# JL7018F8.net
KiCad netlist of a schematic drawn in Altium Designer
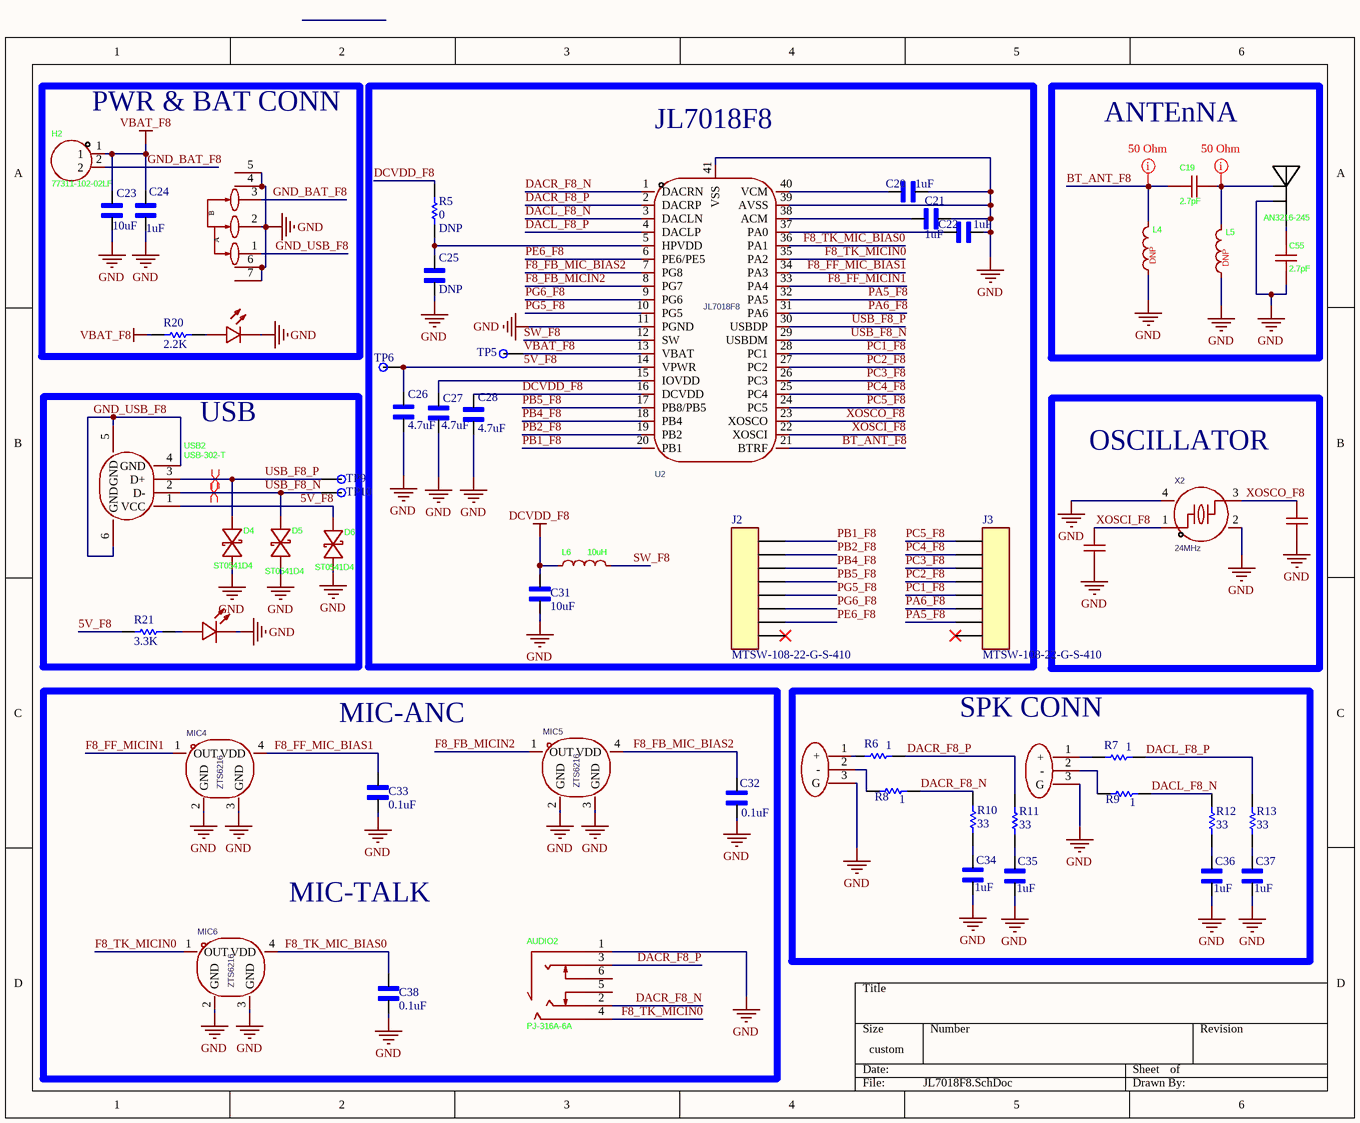
[diagram p0: JL7018F8.SchDoc]

(export (version "E")
  (design (tool "Eeschema 10.0.6"))
  (components
    (comp (ref "ANT2")
      (value "AN3216-245")
      (footprint "CUSTOME ANTEENA")
      (fields (field (name "MANUFACTURER") "Rainsun(霖昱微)") (field (name "POWER") "1W"))
      (libsource (lib "JEILI_DEV_BOARD") (part "AN3216-245"))
    )
    (comp (ref "AUDIO2")
      (value "PJ-316A-6A")
      (footprint "AUDIO-SMD_PJ-316A-6A")
      (fields (field (name "MANUFACTURER") "韩国韩荣"))
      (libsource (lib "JEILI_DEV_BOARD") (part "PJ-316A-6A"))
    )
    (comp (ref "C19")
      (value "2.7pF")
      (footprint "C0603")
      (fields (field (name "MANUFACTURER") "FH(风华)") (field (name "MANUFACTURER PART") "0603CG2R7C500NT"))
      (libsource (lib "JEILI_DEV_BOARD") (part "0603CG2R7C500NT"))
    )
    (comp (ref "C20")
      (value "1uF")
      (footprint "CAPC3216X170N")
      (libsource (lib "JEILI_DEV_BOARD") (part "CAP_1uF"))
    )
    (comp (ref "C21")
      (value "1uF")
      (footprint "CAPC3216X170N")
      (libsource (lib "JEILI_DEV_BOARD") (part "CAP_1uF"))
    )
    (comp (ref "C22")
      (value "1uF")
      (footprint "CAPC3216X170N")
      (libsource (lib "JEILI_DEV_BOARD") (part "CAP_1uF"))
    )
    (comp (ref "C23")
      (value "10uF")
      (footprint "CAPC3216X170N")
      (libsource (lib "JEILI_DEV_BOARD") (part "CAP_10F"))
    )
    (comp (ref "C24") (value "1uF") (footprint "CAPC3216X170N") (libsource (lib "") (part "CAP_1uF_1")))
    (comp (ref "C25")
      (value "DNP")
      (footprint "CAPC3216X170N")
      (fields (field (name "Comment") "1uF"))
      (libsource (lib "") (part "CAP_1uF_1"))
    )
    (comp (ref "C26")
      (value "4.7uF")
      (footprint "CAPC3216X170N")
      (fields (field (name "Comment") "1uF"))
      (libsource (lib "") (part "CAP_1uF_1"))
    )
    (comp (ref "C27")
      (value "4.7uF")
      (footprint "CAPC3216X170N")
      (fields (field (name "Comment") "1uF"))
      (libsource (lib "") (part "CAP_1uF_1"))
    )
    (comp (ref "C28")
      (value "4.7uF")
      (footprint "CAPC3216X170N")
      (fields (field (name "Comment") "1uF"))
      (libsource (lib "") (part "CAP_1uF_1"))
    )
    (comp (ref "C29")
      (value "12pF")
      (footprint "CAPC3216X170N")
      (fields
        (field (name "MANUFACTURER") "FH(风华)")
        (field (name "MANUFACTURER PART") "0402CG120J500NT")
        (field (name "TOLERANCE") "±5%")
      )
      (libsource (lib "JEILI_DEV_BOARD") (part "0402CG120J500NT"))
    )
    (comp (ref "C30")
      (value "12pF")
      (footprint "CAPC3216X170N")
      (fields
        (field (name "MANUFACTURER") "FH(风华)")
        (field (name "MANUFACTURER PART") "0402CG120J500NT")
        (field (name "TOLERANCE") "±5%")
      )
      (libsource (lib "JEILI_DEV_BOARD") (part "0402CG120J500NT"))
    )
    (comp (ref "C31")
      (value "10uF")
      (footprint "CAPC3216X170N")
      (libsource (lib "JEILI_DEV_BOARD") (part "CAP_10F"))
    )
    (comp (ref "C32")
      (value "0.1uF")
      (footprint "CAPC3216X170N")
      (description "100nF 10V X7R ±5% 0402 Multilayer Ceramic Capacitors MLCC - SMD/SMT ROHS")
      (fields (field (name "MANUFACTURER") "Walsin Tech Corp") (field (name "MFR.PART #") "0402B104J100CT"))
      (libsource (lib "Glasses_EEG_V2.0") (part "CAP_0.1uF"))
    )
    (comp (ref "C33")
      (value "0.1uF")
      (footprint "CAPC3216X170N")
      (description "100nF 10V X7R ±5% 0402 Multilayer Ceramic Capacitors MLCC - SMD/SMT ROHS")
      (fields (field (name "MANUFACTURER") "Walsin Tech Corp") (field (name "MFR.PART #") "0402B104J100CT"))
      (libsource (lib "Glasses_EEG_V2.0") (part "CAP_0.1uF"))
    )
    (comp (ref "C34") (value "1uF") (footprint "CAPC3216X170N") (libsource (lib "") (part "CAP_1uF_2")))
    (comp (ref "C35") (value "1uF") (footprint "CAPC3216X170N") (libsource (lib "") (part "CAP_1uF_2")))
    (comp (ref "C36") (value "1uF") (footprint "CAPC3216X170N") (libsource (lib "") (part "CAP_1uF_2")))
    (comp (ref "C37") (value "1uF") (footprint "CAPC3216X170N") (libsource (lib "") (part "CAP_1uF_2")))
    (comp (ref "C38")
      (value "0.1uF")
      (footprint "CAPC3216X170N")
      (description "100nF 10V X7R ±5% 0402 Multilayer Ceramic Capacitors MLCC - SMD/SMT ROHS")
      (fields (field (name "MANUFACTURER") "Walsin Tech Corp") (field (name "MFR.PART #") "0402B104J100CT"))
      (libsource (lib "Glasses_EEG_V2.0") (part "CAP_0.1uF"))
    )
    (comp (ref "C55")
      (value "2.7pF")
      (footprint "C0402")
      (fields (field (name "MANUFACTURER") "FH(风华)") (field (name "MANUFACTURER PART") "0603CG2R7C500NT"))
      (libsource (lib "JEILI_DEV_BOARD") (part "0603CG2R7C500NT"))
    )
    (comp (ref "D4")
      (value "ST0541D4")
      (footprint "DFN1006-BI")
      (fields (field (name "MANUFACTURER") "Leiditech(雷卯电子)"))
      (libsource (lib "JEILI_DEV_BOARD") (part "ST0541D4"))
    )
    (comp (ref "D5")
      (value "ST0541D4")
      (footprint "DFN1006-BI")
      (fields (field (name "MANUFACTURER") "Leiditech(雷卯电子)"))
      (libsource (lib "JEILI_DEV_BOARD") (part "ST0541D4"))
    )
    (comp (ref "D6")
      (value "ST0541D4")
      (footprint "DFN1006-BI")
      (fields (field (name "MANUFACTURER") "Leiditech(雷卯电子)"))
      (libsource (lib "JEILI_DEV_BOARD") (part "ST0541D4"))
    )
    (comp (ref "H2")
      (value "77311-102-02LF")
      (footprint "HDR-TH_2P-P2.54-V-M-1")
      (fields (field (name "MANUFACTURER") "Amphenol"))
      (libsource (lib "JEILI_DEV_BOARD") (part "77311-102-02LF"))
    )
    (comp (ref "J2")
      (value "MTSW-108-22-G-S-410")
      (footprint "SAMTEC_MTSW-108-22-G-S-410")
      (libsource (lib "JEILI_DEV_BOARD") (part "MTSW-108-22-G-S-410"))
    )
    (comp (ref "J3")
      (value "MTSW-108-22-G-S-410")
      (footprint "SAMTEC_MTSW-108-22-G-S-410")
      (libsource (lib "") (part "MTSW-108-22-G-S-410_1"))
    )
    (comp (ref "L4")
      (value "DNP")
      (footprint "L0603")
      (fields
        (field (name "MANUFACTURER") "muRata(村田)")
        (field (name "MANUFACTURER PART") "DFE18SAN1R0ME0L")
        (field (name "TOLERANCE") "±20%")
      )
      (libsource (lib "JEILI_DEV_BOARD") (part "33nH"))
    )
    (comp (ref "L5")
      (value "DNP")
      (footprint "L0603")
      (fields
        (field (name "MANUFACTURER") "muRata(村田)")
        (field (name "MANUFACTURER PART") "DFE18SAN1R0ME0L")
        (field (name "TOLERANCE") "±20%")
      )
      (libsource (lib "JEILI_DEV_BOARD") (part "33nH"))
    )
    (comp (ref "L6") (value "10uH") (footprint "L0603") (libsource (lib "JEILI_DEV_BOARD") (part "10uH")))
    (comp (ref "LED3")
      (value "LTST-C191GKT")
      (footprint "LED0603-R-RD_GREEN")
      (fields (field (name "MANUFACTURER") "LITEON(光宝)"))
      (libsource (lib "JEILI_DEV_BOARD") (part "LTST-C191GKT"))
    )
    (comp (ref "LED4")
      (value "KT-0603R")
      (footprint "LED0603-RD")
      (fields (field (name "MANUFACTURER") "KENTO"))
      (libsource (lib "JEILI_DEV_BOARD") (part "KT-0603R"))
    )
    (comp (ref "MIC4")
      (value "ZTS6216")
      (footprint "MIC-SMD_4P-L2.8-W1.9-P1.84-TL")
      (fields (field (name "MANUFACTURER") "ZILLTEK(钰太)"))
      (libsource (lib "Glasses_EEG_V2.0") (part "ZTS6216"))
    )
    (comp (ref "MIC5")
      (value "ZTS6216")
      (footprint "MIC-SMD_4P-L2.8-W1.9-P1.84-TL")
      (fields (field (name "MANUFACTURER") "ZILLTEK(钰太)"))
      (libsource (lib "Glasses_EEG_V2.0") (part "ZTS6216"))
    )
    (comp (ref "MIC6")
      (value "ZTS6216")
      (footprint "MIC-SMD_4P-L2.8-W1.9-P1.84-TL")
      (fields (field (name "MANUFACTURER") "ZILLTEK(钰太)"))
      (libsource (lib "Glasses_EEG_V2.0") (part "ZTS6216"))
    )
    (comp (ref "P2")
      (value "1.27-1*3P针")
      (footprint "HDR-TH_3P-P1.27-V-M-1")
      (fields (field (name "MANUFACTURER") "BOOMELE(博穆精密)"))
      (libsource (lib "JEILI_DEV_BOARD") (part "1.27-1*3P针"))
    )
    (comp (ref "P3")
      (value "1.27-1*3P针")
      (footprint "HDR-TH_3P-P1.27-V-M-1")
      (fields (field (name "MANUFACTURER") "BOOMELE(博穆精密)"))
      (libsource (lib "JEILI_DEV_BOARD") (part "1.27-1*3P针"))
    )
    (comp (ref "R5")
      (value "DNP")
      (footprint "R0603")
      (description "-55℃~+155℃ 0Ω 50V 62.5mW Thick Film Resistor ±5% 0402 Chip Resistor - Surface Mount ROHS")
      (fields
        (field (name "MANUFACTURER") "RALEC")
        (field (name "MFR.PART #") "RTT02000JTH")
        (field (name "ALTIUM_VALUE") "0")
      )
      (libsource (lib "JEILI_DEV_BOARD") (part "RES_0"))
    )
    (comp (ref "R6")
      (value "1")
      (footprint "R0603")
      (fields
        (field (name "MANUFACTURER") "YAGEO")
        (field (name "MFR.PART #") "RC0402JR-0733RL")
        (field (name "JLCPCB PART #") "C137880")
      )
      (libsource (lib "JEILI_DEV_BOARD") (part "RES_1"))
    )
    (comp (ref "R7")
      (value "1")
      (footprint "R0603")
      (fields
        (field (name "MANUFACTURER") "YAGEO")
        (field (name "MFR.PART #") "RC0402JR-0733RL")
        (field (name "JLCPCB PART #") "C137880")
      )
      (libsource (lib "JEILI_DEV_BOARD") (part "RES_1"))
    )
    (comp (ref "R8")
      (value "1")
      (footprint "R0603")
      (fields
        (field (name "MANUFACTURER") "YAGEO")
        (field (name "MFR.PART #") "RC0402JR-0733RL")
        (field (name "JLCPCB PART #") "C137880")
      )
      (libsource (lib "JEILI_DEV_BOARD") (part "RES_1"))
    )
    (comp (ref "R9")
      (value "1")
      (footprint "R0603")
      (fields
        (field (name "MANUFACTURER") "YAGEO")
        (field (name "MFR.PART #") "RC0402JR-0733RL")
        (field (name "JLCPCB PART #") "C137880")
      )
      (libsource (lib "JEILI_DEV_BOARD") (part "RES_1"))
    )
    (comp (ref "R10")
      (value "33")
      (footprint "R0603")
      (fields
        (field (name "MANUFACTURER") "YAGEO")
        (field (name "MFR.PART #") "RC0402JR-0733RL")
        (field (name "JLCPCB PART #") "C137880")
      )
      (libsource (lib "JEILI_DEV_BOARD") (part "RES_33"))
    )
    (comp (ref "R11")
      (value "33")
      (footprint "R0603")
      (fields
        (field (name "MANUFACTURER") "YAGEO")
        (field (name "MFR.PART #") "RC0402JR-0733RL")
        (field (name "JLCPCB PART #") "C137880")
      )
      (libsource (lib "JEILI_DEV_BOARD") (part "RES_33"))
    )
    (comp (ref "R12")
      (value "33")
      (footprint "R0603")
      (fields
        (field (name "MANUFACTURER") "YAGEO")
        (field (name "MFR.PART #") "RC0402JR-0733RL")
        (field (name "JLCPCB PART #") "C137880")
      )
      (libsource (lib "JEILI_DEV_BOARD") (part "RES_33"))
    )
    (comp (ref "R13")
      (value "33")
      (footprint "R0603")
      (fields
        (field (name "MANUFACTURER") "YAGEO")
        (field (name "MFR.PART #") "RC0402JR-0733RL")
        (field (name "JLCPCB PART #") "C137880")
      )
      (libsource (lib "JEILI_DEV_BOARD") (part "RES_33"))
    )
    (comp (ref "R20")
      (value "2.2K")
      (footprint "R1206")
      (fields
        (field (name "MANUFACTURER") "YAGEO")
        (field (name "MFR.PART #") "RC0402JR-0733RL")
        (field (name "JLCPCB PART #") "C137880")
      )
      (libsource (lib "JEILI_DEV_BOARD") (part "RES_2.2K"))
    )
    (comp (ref "R21")
      (value "3.3K")
      (footprint "R1206")
      (fields
        (field (name "MANUFACTURER") "YAGEO")
        (field (name "MFR.PART #") "RC0402JR-0733RL")
        (field (name "JLCPCB PART #") "C137880")
      )
      (libsource (lib "JEILI_DEV_BOARD") (part "RES_3.3K"))
    )
    (comp (ref "SW2")
      (value "MK-12C02-G015")
      (footprint "SW-SMD_G-SWITCH_MK-12C02-G015")
      (fields (field (name "MANUFACTURER") "G-Switch(品赞)"))
      (libsource (lib "JEILI_DEV_BOARD") (part "MK-12C02-G015_C2911519"))
    )
    (comp (ref "TP5")
      (value "TP_1")
      (footprint "TP")
      (description "test point")
      (libsource (lib "JEILI_DEV_BOARD") (part "TP_1"))
    )
    (comp (ref "TP6")
      (value "TP_1")
      (footprint "TP")
      (description "test point")
      (libsource (lib "JEILI_DEV_BOARD") (part "TP_1"))
    )
    (comp (ref "TP9")
      (value "TP")
      (footprint "TP")
      (description "test point")
      (libsource (lib "JEILI_DEV_BOARD") (part "TP"))
    )
    (comp (ref "TP10")
      (value "TP")
      (footprint "TP")
      (description "test point")
      (libsource (lib "JEILI_DEV_BOARD") (part "TP"))
    )
    (comp (ref "U2")
      (value "JL7018F8")
      (footprint "QFN-40_L5.0-W5.0-P0.40-TL-EP3.6")
      (fields (field (name "MANUFACTURER") "JL(杰理)"))
      (libsource (lib "JEILI_DEV_BOARD") (part "JL7018F8"))
    )
    (comp (ref "USB2")
      (value "USB-302-T")
      (footprint "USB-A-TH_USB-302-T")
      (fields (field (name "MANUFACTURER") "SOFNG(硕方)"))
      (libsource (lib "JEILI_DEV_BOARD") (part "USB-302-T"))
    )
    (comp (ref "X2")
      (value "24MHz")
      (footprint "CRYSTAL-SMD_4P-L2.0-W1.6-BL-A")
      (fields
        (field (name "MANUFACTURER") "YXC(扬兴晶振)")
        (field (name "MANUFACTURER PART") "XL7EL89CKI-111YLC-24M")
      )
      (libsource (lib "Glasses_EEG_V2.0") (part "XL7EL89CKI-111YLC-24M"))
    )
  )
  (nets
    (net (code "1") (name "/5V_F8") (class "Default")
      (node (ref "C26") (pin "1") (pinfunction "1_1") (pintype "passive"))
      (node (ref "D6") (pin "2") (pinfunction "2_2") (pintype "passive"))
      (node (ref "R21") (pin "2") (pinfunction "2_2") (pintype "passive"))
      (node (ref "TP6") (pin "1") (pinfunction "1_1") (pintype "passive"))
      (node (ref "U2") (pin "14") (pinfunction "VPWR_14") (pintype "passive"))
      (node (ref "USB2") (pin "1") (pinfunction "VCC_1") (pintype "passive"))
    )
    (net (code "2") (name "/BT_ANT_F8") (class "Default")
      (node (ref "C19") (pin "1") (pinfunction "1_1") (pintype "passive"))
      (node (ref "L4") (pin "2") (pinfunction "2_2") (pintype "passive"))
      (node (ref "U2") (pin "21") (pinfunction "BTRF_21") (pintype "passive"))
    )
    (net (code "3") (name "/DACL_F8_N") (class "Default")
      (node (ref "R12") (pin "1") (pinfunction "1_1") (pintype "passive"))
      (node (ref "R9") (pin "1") (pinfunction "1_1") (pintype "passive"))
      (node (ref "U2") (pin "3") (pinfunction "DACLN_3") (pintype "passive"))
    )
    (net (code "4") (name "/DACL_F8_P") (class "Default")
      (node (ref "R13") (pin "1") (pinfunction "1_1") (pintype "passive"))
      (node (ref "R7") (pin "1") (pinfunction "1_1") (pintype "passive"))
      (node (ref "U2") (pin "4") (pinfunction "DACLP_4") (pintype "passive"))
    )
    (net (code "5") (name "/DACR_F8_N") (class "Default")
      (node (ref "AUDIO2") (pin "2") (pinfunction "2_2") (pintype "passive"))
      (node (ref "R10") (pin "1") (pinfunction "1_1") (pintype "passive"))
      (node (ref "R8") (pin "1") (pinfunction "1_1") (pintype "passive"))
      (node (ref "U2") (pin "1") (pinfunction "DACRN_1") (pintype "passive"))
    )
    (net (code "6") (name "/DACR_F8_P") (class "Default")
      (node (ref "AUDIO2") (pin "3") (pinfunction "3_3") (pintype "passive"))
      (node (ref "R11") (pin "1") (pinfunction "1_1") (pintype "passive"))
      (node (ref "R6") (pin "1") (pinfunction "1_1") (pintype "passive"))
      (node (ref "U2") (pin "2") (pinfunction "DACRP_2") (pintype "passive"))
    )
    (net (code "7") (name "/F8_FB_MICIN2") (class "Default")
      (node (ref "MIC5") (pin "1") (pinfunction "OUT_1") (pintype "passive"))
      (node (ref "U2") (pin "8") (pinfunction "PG7_8") (pintype "passive"))
    )
    (net (code "8") (name "/F8_FB_MIC_BIAS2") (class "Default")
      (node (ref "C32") (pin "2") (pinfunction "2_2") (pintype "passive"))
      (node (ref "MIC5") (pin "4") (pinfunction "VDD_4") (pintype "passive"))
      (node (ref "U2") (pin "7") (pinfunction "PG8_7") (pintype "passive"))
    )
    (net (code "9") (name "/F8_FF_MICIN1") (class "Default")
      (node (ref "MIC4") (pin "1") (pinfunction "OUT_1") (pintype "passive"))
      (node (ref "U2") (pin "33") (pinfunction "PA4_33") (pintype "passive"))
    )
    (net (code "10") (name "/F8_FF_MIC_BIAS1") (class "Default")
      (node (ref "C33") (pin "2") (pinfunction "2_2") (pintype "passive"))
      (node (ref "MIC4") (pin "4") (pinfunction "VDD_4") (pintype "passive"))
      (node (ref "U2") (pin "34") (pinfunction "PA3_34") (pintype "passive"))
    )
    (net (code "11") (name "/F8_TK_MICIN0") (class "Default")
      (node (ref "AUDIO2") (pin "4") (pinfunction "4_4") (pintype "passive"))
      (node (ref "MIC6") (pin "1") (pinfunction "OUT_1") (pintype "passive"))
      (node (ref "U2") (pin "35") (pinfunction "PA2_35") (pintype "passive"))
    )
    (net (code "12") (name "/F8_TK_MIC_BIAS0") (class "Default")
      (node (ref "C38") (pin "2") (pinfunction "2_2") (pintype "passive"))
      (node (ref "MIC6") (pin "4") (pinfunction "VDD_4") (pintype "passive"))
      (node (ref "U2") (pin "36") (pinfunction "PA1_36") (pintype "passive"))
    )
    (net (code "13") (name "/GND_BAT_F8") (class "Default")
      (node (ref "H2") (pin "2") (pinfunction "2_2") (pintype "passive"))
      (node (ref "SW2") (pin "3") (pinfunction "3_3") (pintype "passive"))
    )
    (net (code "14") (name "/GND_USB_F8") (class "Default")
      (node (ref "SW2") (pin "1") (pinfunction "1_1") (pintype "passive"))
      (node (ref "USB2") (pin "4") (pinfunction "GND_4") (pintype "passive"))
      (node (ref "USB2") (pin "5") (pinfunction "GND_5") (pintype "passive"))
      (node (ref "USB2") (pin "6") (pinfunction "GND_6") (pintype "passive"))
    )
    (net (code "15") (name "/PA5_F8") (class "Default")
      (node (ref "J3") (pin "07") (pinfunction "07_07") (pintype "passive"))
      (node (ref "U2") (pin "32") (pinfunction "PA5_32") (pintype "passive"))
    )
    (net (code "16") (name "/PA6_F8") (class "Default")
      (node (ref "J3") (pin "06") (pinfunction "06_06") (pintype "passive"))
      (node (ref "U2") (pin "31") (pinfunction "PA6_31") (pintype "passive"))
    )
    (net (code "17") (name "/PB1_F8") (class "Default")
      (node (ref "J2") (pin "01") (pinfunction "01_01") (pintype "passive"))
      (node (ref "U2") (pin "20") (pinfunction "PB1_20") (pintype "passive"))
    )
    (net (code "18") (name "/PB2_F8") (class "Default")
      (node (ref "J2") (pin "02") (pinfunction "02_02") (pintype "passive"))
      (node (ref "U2") (pin "19") (pinfunction "PB2_19") (pintype "passive"))
    )
    (net (code "19") (name "/PB4_F8") (class "Default")
      (node (ref "J2") (pin "03") (pinfunction "03_03") (pintype "passive"))
      (node (ref "U2") (pin "18") (pinfunction "PB4_18") (pintype "passive"))
    )
    (net (code "20") (name "/PB5_F8") (class "Default")
      (node (ref "J2") (pin "04") (pinfunction "04_04") (pintype "passive"))
      (node (ref "U2") (pin "17") (pinfunction "PB8/PB5_17") (pintype "passive"))
    )
    (net (code "21") (name "/PC1_F8") (class "Default")
      (node (ref "J3") (pin "05") (pinfunction "05_05") (pintype "passive"))
      (node (ref "U2") (pin "28") (pinfunction "PC1_28") (pintype "passive"))
    )
    (net (code "22") (name "/PC2_F8") (class "Default")
      (node (ref "J3") (pin "04") (pinfunction "04_04") (pintype "passive"))
      (node (ref "U2") (pin "27") (pinfunction "PC2_27") (pintype "passive"))
    )
    (net (code "23") (name "/PC3_F8") (class "Default")
      (node (ref "J3") (pin "03") (pinfunction "03_03") (pintype "passive"))
      (node (ref "U2") (pin "26") (pinfunction "PC3_26") (pintype "passive"))
    )
    (net (code "24") (name "/PC4_F8") (class "Default")
      (node (ref "J3") (pin "02") (pinfunction "02_02") (pintype "passive"))
      (node (ref "U2") (pin "25") (pinfunction "PC4_25") (pintype "passive"))
    )
    (net (code "25") (name "/PC5_F8") (class "Default")
      (node (ref "J3") (pin "01") (pinfunction "01_01") (pintype "passive"))
      (node (ref "U2") (pin "24") (pinfunction "PC5_24") (pintype "passive"))
    )
    (net (code "26") (name "/PE6_F8") (class "Default")
      (node (ref "J2") (pin "07") (pinfunction "07_07") (pintype "passive"))
      (node (ref "U2") (pin "6") (pinfunction "PE6/PE5_6") (pintype "passive"))
    )
    (net (code "27") (name "/PG5_F8") (class "Default")
      (node (ref "J2") (pin "05") (pinfunction "05_05") (pintype "passive"))
      (node (ref "U2") (pin "10") (pinfunction "PG5_10") (pintype "passive"))
    )
    (net (code "28") (name "/PG6_F8") (class "Default")
      (node (ref "J2") (pin "06") (pinfunction "06_06") (pintype "passive"))
      (node (ref "U2") (pin "9") (pinfunction "PG6_9") (pintype "passive"))
    )
    (net (code "29") (name "/SW_F8") (class "Default")
      (node (ref "L6") (pin "2") (pinfunction "2_2") (pintype "passive"))
      (node (ref "U2") (pin "12") (pinfunction "SW_12") (pintype "passive"))
    )
    (net (code "30") (name "/USB_F8_N") (class "Default")
      (node (ref "D5") (pin "2") (pinfunction "2_2") (pintype "passive"))
      (node (ref "TP10") (pin "1") (pinfunction "1_1") (pintype "passive"))
      (node (ref "U2") (pin "29") (pinfunction "USBDM_29") (pintype "passive"))
      (node (ref "USB2") (pin "2") (pinfunction "D-_2") (pintype "passive"))
    )
    (net (code "31") (name "/USB_F8_P") (class "Default")
      (node (ref "D4") (pin "2") (pinfunction "2_2") (pintype "passive"))
      (node (ref "TP9") (pin "1") (pinfunction "1_1") (pintype "passive"))
      (node (ref "U2") (pin "30") (pinfunction "USBDP_30") (pintype "passive"))
      (node (ref "USB2") (pin "3") (pinfunction "D+_3") (pintype "passive"))
    )
    (net (code "32") (name "/XOSCI_F8") (class "Default")
      (node (ref "C30") (pin "2") (pinfunction "2_2") (pintype "passive"))
      (node (ref "U2") (pin "22") (pinfunction "XOSCI_22") (pintype "passive"))
      (node (ref "X2") (pin "1") (pinfunction "1_1") (pintype "passive"))
    )
    (net (code "33") (name "/XOSCO_F8") (class "Default")
      (node (ref "C29") (pin "2") (pinfunction "2_2") (pintype "passive"))
      (node (ref "U2") (pin "23") (pinfunction "XOSCO_23") (pintype "passive"))
      (node (ref "X2") (pin "3") (pinfunction "3_3") (pintype "passive"))
    )
    (net (code "34") (name "DCVDD_F8") (class "Default")
      (node (ref "C28") (pin "1") (pinfunction "1_1") (pintype "passive"))
      (node (ref "C31") (pin "2") (pinfunction "2_2") (pintype "passive"))
      (node (ref "L6") (pin "1") (pinfunction "1_1") (pintype "passive"))
      (node (ref "R5") (pin "2") (pinfunction "2_2") (pintype "passive"))
      (node (ref "U2") (pin "16") (pinfunction "DCVDD_16") (pintype "passive"))
    )
    (net (code "35") (name "GND") (class "Default")
      (node (ref "ANT2") (pin "2") (pinfunction "2_2") (pintype "passive"))
      (node (ref "AUDIO2") (pin "1") (pinfunction "1_1") (pintype "passive"))
      (node (ref "C20") (pin "2") (pinfunction "2_2") (pintype "passive"))
      (node (ref "C21") (pin "2") (pinfunction "2_2") (pintype "passive"))
      (node (ref "C22") (pin "2") (pinfunction "2_2") (pintype "passive"))
      (node (ref "C23") (pin "1") (pinfunction "1_1") (pintype "passive"))
      (node (ref "C24") (pin "2") (pinfunction "2_2") (pintype "passive"))
      (node (ref "C25") (pin "2") (pinfunction "2_2") (pintype "passive"))
      (node (ref "C26") (pin "2") (pinfunction "2_2") (pintype "passive"))
      (node (ref "C27") (pin "2") (pinfunction "2_2") (pintype "passive"))
      (node (ref "C28") (pin "2") (pinfunction "2_2") (pintype "passive"))
      (node (ref "C29") (pin "1") (pinfunction "1_1") (pintype "passive"))
      (node (ref "C30") (pin "1") (pinfunction "1_1") (pintype "passive"))
      (node (ref "C31") (pin "1") (pinfunction "1_1") (pintype "passive"))
      (node (ref "C32") (pin "1") (pinfunction "1_1") (pintype "passive"))
      (node (ref "C33") (pin "1") (pinfunction "1_1") (pintype "passive"))
      (node (ref "C34") (pin "1") (pinfunction "1_1") (pintype "passive"))
      (node (ref "C35") (pin "1") (pinfunction "1_1") (pintype "passive"))
      (node (ref "C36") (pin "1") (pinfunction "1_1") (pintype "passive"))
      (node (ref "C37") (pin "1") (pinfunction "1_1") (pintype "passive"))
      (node (ref "C38") (pin "1") (pinfunction "1_1") (pintype "passive"))
      (node (ref "C55") (pin "1") (pinfunction "1_1") (pintype "passive"))
      (node (ref "D4") (pin "1") (pinfunction "1_1") (pintype "passive"))
      (node (ref "D5") (pin "1") (pinfunction "1_1") (pintype "passive"))
      (node (ref "D6") (pin "1") (pinfunction "1_1") (pintype "passive"))
      (node (ref "L4") (pin "1") (pinfunction "1_1") (pintype "passive"))
      (node (ref "L5") (pin "1") (pinfunction "1_1") (pintype "passive"))
      (node (ref "LED3") (pin "2") (pinfunction "C_2") (pintype "passive"))
      (node (ref "LED4") (pin "1") (pinfunction "K_1") (pintype "passive"))
      (node (ref "MIC4") (pin "2") (pinfunction "GND_2") (pintype "passive"))
      (node (ref "MIC4") (pin "3") (pinfunction "GND_3") (pintype "passive"))
      (node (ref "MIC5") (pin "2") (pinfunction "GND_2") (pintype "passive"))
      (node (ref "MIC5") (pin "3") (pinfunction "GND_3") (pintype "passive"))
      (node (ref "MIC6") (pin "2") (pinfunction "GND_2") (pintype "passive"))
      (node (ref "MIC6") (pin "3") (pinfunction "GND_3") (pintype "passive"))
      (node (ref "P2") (pin "3") (pinfunction "G_3") (pintype "passive"))
      (node (ref "P3") (pin "3") (pinfunction "G_3") (pintype "passive"))
      (node (ref "SW2") (pin "2") (pinfunction "2_2") (pintype "passive"))
      (node (ref "SW2") (pin "4") (pinfunction "4_4") (pintype "passive"))
      (node (ref "SW2") (pin "5") (pinfunction "5_5") (pintype "passive"))
      (node (ref "SW2") (pin "6") (pinfunction "6_6") (pintype "passive"))
      (node (ref "SW2") (pin "7") (pinfunction "7_7") (pintype "passive"))
      (node (ref "U2") (pin "11") (pinfunction "PGND_11") (pintype "passive"))
      (node (ref "U2") (pin "39") (pinfunction "AVSS_39") (pintype "passive"))
      (node (ref "U2") (pin "41") (pinfunction "VSS_41") (pintype "passive"))
      (node (ref "X2") (pin "2") (pinfunction "GND_2") (pintype "passive"))
      (node (ref "X2") (pin "4") (pinfunction "GND_4") (pintype "passive"))
    )
    (net (code "36") (name "Net-(ANT2-Pad1)") (class "Default")
      (node (ref "ANT2") (pin "1") (pinfunction "1_1") (pintype "passive"))
      (node (ref "C19") (pin "2") (pinfunction "2_2") (pintype "passive"))
      (node (ref "L5") (pin "2") (pinfunction "2_2") (pintype "passive"))
    )
    (net (code "37") (name "Net-(ANT2-Pad3)") (class "Default")
      (node (ref "ANT2") (pin "3") (pinfunction "3_3") (pintype "passive"))
      (node (ref "C55") (pin "2") (pinfunction "2_2") (pintype "passive"))
    )
    (net (code "38") (name "Net-(C34-Pad2)") (class "Default")
      (node (ref "C34") (pin "2") (pinfunction "2_2") (pintype "passive"))
      (node (ref "R10") (pin "2") (pinfunction "2_2") (pintype "passive"))
    )
    (net (code "39") (name "Net-(C35-Pad2)") (class "Default")
      (node (ref "C35") (pin "2") (pinfunction "2_2") (pintype "passive"))
      (node (ref "R11") (pin "2") (pinfunction "2_2") (pintype "passive"))
    )
    (net (code "40") (name "Net-(C36-Pad2)") (class "Default")
      (node (ref "C36") (pin "2") (pinfunction "2_2") (pintype "passive"))
      (node (ref "R12") (pin "2") (pinfunction "2_2") (pintype "passive"))
    )
    (net (code "41") (name "Net-(C37-Pad2)") (class "Default")
      (node (ref "C37") (pin "2") (pinfunction "2_2") (pintype "passive"))
      (node (ref "R13") (pin "2") (pinfunction "2_2") (pintype "passive"))
    )
    (net (code "42") (name "Net-(LED3-A)") (class "Default")
      (node (ref "LED3") (pin "1") (pinfunction "A_1") (pintype "passive"))
      (node (ref "R20") (pin "1") (pinfunction "1_1") (pintype "passive"))
    )
    (net (code "43") (name "Net-(LED4-A)") (class "Default")
      (node (ref "LED4") (pin "2") (pinfunction "A_2") (pintype "passive"))
      (node (ref "R21") (pin "1") (pinfunction "1_1") (pintype "passive"))
    )
    (net (code "44") (name "Net-(P2-+)") (class "Default")
      (node (ref "P2") (pin "1") (pinfunction "+_1") (pintype "passive"))
      (node (ref "R6") (pin "2") (pinfunction "2_2") (pintype "passive"))
    )
    (net (code "45") (name "Net-(P2--)") (class "Default")
      (node (ref "P2") (pin "2") (pinfunction "-_2") (pintype "passive"))
      (node (ref "R8") (pin "2") (pinfunction "2_2") (pintype "passive"))
    )
    (net (code "46") (name "Net-(P3-+)") (class "Default")
      (node (ref "P3") (pin "1") (pinfunction "+_1") (pintype "passive"))
      (node (ref "R7") (pin "2") (pinfunction "2_2") (pintype "passive"))
    )
    (net (code "47") (name "Net-(P3--)") (class "Default")
      (node (ref "P3") (pin "2") (pinfunction "-_2") (pintype "passive"))
      (node (ref "R9") (pin "2") (pinfunction "2_2") (pintype "passive"))
    )
    (net (code "48") (name "Net-(U2-ACM)") (class "Default")
      (node (ref "C21") (pin "1") (pinfunction "1_1") (pintype "passive"))
      (node (ref "U2") (pin "38") (pinfunction "ACM_38") (pintype "passive"))
    )
    (net (code "49") (name "Net-(U2-HPVDD)") (class "Default")
      (node (ref "C25") (pin "1") (pinfunction "1_1") (pintype "passive"))
      (node (ref "R5") (pin "1") (pinfunction "1_1") (pintype "passive"))
      (node (ref "U2") (pin "5") (pinfunction "HPVDD_5") (pintype "passive"))
    )
    (net (code "50") (name "Net-(U2-IOVDD)") (class "Default")
      (node (ref "C27") (pin "1") (pinfunction "1_1") (pintype "passive"))
      (node (ref "U2") (pin "15") (pinfunction "IOVDD_15") (pintype "passive"))
    )
    (net (code "51") (name "Net-(U2-PA0)") (class "Default")
      (node (ref "C22") (pin "1") (pinfunction "1_1") (pintype "passive"))
      (node (ref "U2") (pin "37") (pinfunction "PA0_37") (pintype "passive"))
    )
    (net (code "52") (name "Net-(U2-VCM)") (class "Default")
      (node (ref "C20") (pin "1") (pinfunction "1_1") (pintype "passive"))
      (node (ref "U2") (pin "40") (pinfunction "VCM_40") (pintype "passive"))
    )
    (net (code "53") (name "VBAT_F8") (class "Default")
      (node (ref "C23") (pin "2") (pinfunction "2_2") (pintype "passive"))
      (node (ref "C24") (pin "1") (pinfunction "1_1") (pintype "passive"))
      (node (ref "H2") (pin "1") (pinfunction "1_1") (pintype "passive"))
      (node (ref "R20") (pin "2") (pinfunction "2_2") (pintype "passive"))
      (node (ref "TP5") (pin "1") (pinfunction "1_1") (pintype "passive"))
      (node (ref "U2") (pin "13") (pinfunction "VBAT_13") (pintype "passive"))
    )
    (net (code "54") (name "unconnected-(AUDIO2-Pad5)") (class "Default")
      (node (ref "AUDIO2") (pin "5") (pinfunction "5_5") (pintype "passive"))
    )
    (net (code "55") (name "unconnected-(AUDIO2-Pad6)") (class "Default")
      (node (ref "AUDIO2") (pin "6") (pinfunction "6_6") (pintype "passive"))
    )
    (net (code "56") (name "unconnected-(J2-Pad08)") (class "Default")
      (node (ref "J2") (pin "08") (pinfunction "08_08") (pintype "passive+no_connect"))
    )
    (net (code "57") (name "unconnected-(J3-Pad08)") (class "Default")
      (node (ref "J3") (pin "08") (pinfunction "08_08") (pintype "passive+no_connect"))
    )
  )
)
